# io_b.net
KiCad netlist of a schematic drawn in Altium Designer
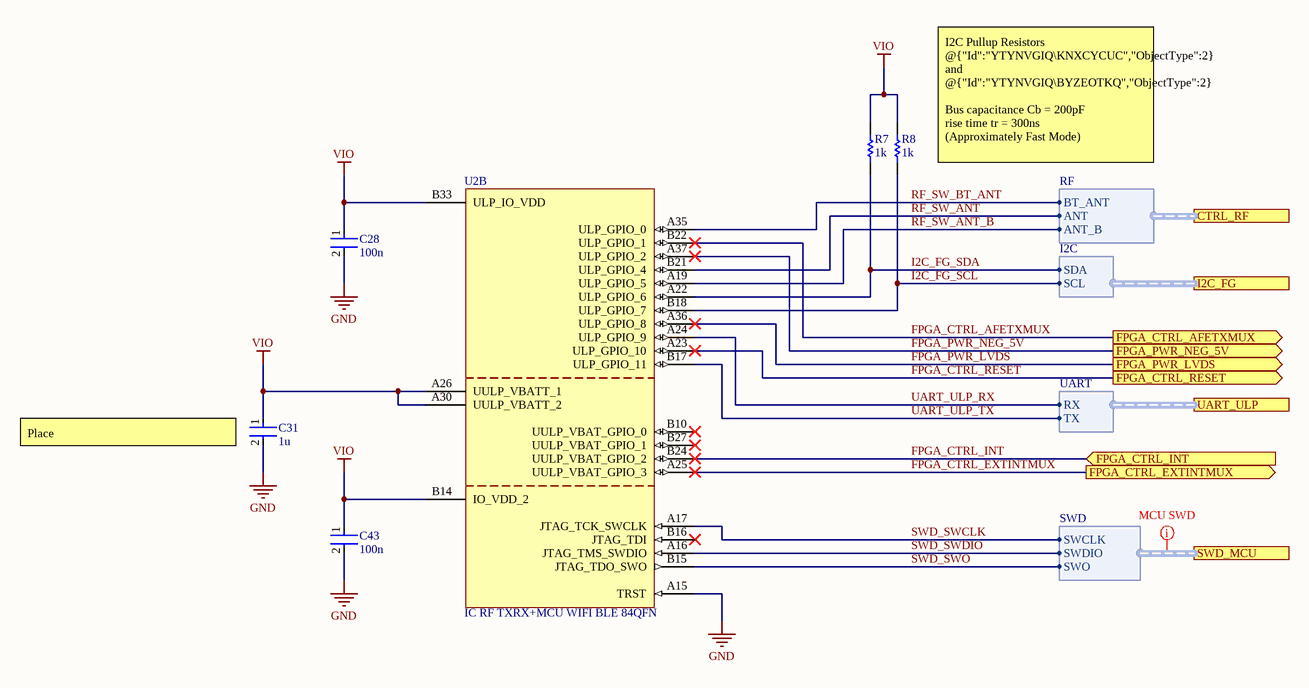
[diagram p0: io_b.SchDoc]

(export (version "E")
  (design (tool "Eeschema 10.0.6"))
  (components
    (comp (ref "C28")
      (value "100n")
      (footprint "FP-GRT155-0_05-MFG")
      (description "Multi-Layer Ceramic Capacitor 100nF 50V X7R ±10% 0402 Paper T/R")
      (libsource (lib "Altium Content Vault") (part "02cd4be3c70576c341d710602a673aa"))
    )
    (comp (ref "C31")
      (value "1u")
      (footprint "FP-GRM155-0_05-MFG")
      (description "Chip Multilayer Ceramic Capacitors for General Purpose, 0402, 1.0uF, X6S, 22%, 10%, 16V")
      (fields (field (name "TOLERANCE") "10%"))
      (libsource (lib "Altium Content Vault") (part "02cd4be3c70576c341d710602a673aa"))
    )
    (comp (ref "C43")
      (value "100n")
      (footprint "FP-GRT155-0_05-MFG")
      (description "Multi-Layer Ceramic Capacitor 100nF 50V X7R ±10% 0402 Paper T/R")
      (libsource (lib "Altium Content Vault") (part "02cd4be3c70576c341d710602a673aa"))
    )
    (comp (ref "R7")
      (value "1k")
      (footprint "RESC1005X40X25LL05T10")
      (fields (field (name "MANUFACTURER") "Yageo") (field (name "PART NUMBER") "RC0402FR-131KL"))
      (libsource (lib "Altium Content Vault") (part "RES"))
    )
    (comp (ref "R8")
      (value "1k")
      (footprint "RESC1005X40X25LL05T10")
      (fields (field (name "MANUFACTURER") "Yageo") (field (name "PART NUMBER") "RC0402FR-131KL"))
      (libsource (lib "Altium Content Vault") (part "RES"))
    )
    (comp (ref "U2")
      (value "IC RF TXRX+MCU WIFI BLE 84QFN")
      (footprint "SIWG917M110LGTBA")
      (libsource (lib "SiWG917") (part "SIWG917"))
    )
  )
  (nets
    (net (code "5") (name "/FPGA_CTRL_AFETXMUX") (class "Default")
      (node (ref "U2") (pin "B22") (pinfunction "ULP_GPIO_1_B22") (pintype "bidirectional+no_connect"))
    )
    (net (code "6") (name "/FPGA_CTRL_EXTINTMUX") (class "Default")
      (node (ref "U2") (pin "A25") (pinfunction "UULP_VBAT_GPIO_3_A25") (pintype "bidirectional+no_connect"))
    )
    (net (code "7") (name "/FPGA_CTRL_INT") (class "Default")
      (node (ref "U2") (pin "B24") (pinfunction "UULP_VBAT_GPIO_2_B24") (pintype "bidirectional+no_connect"))
    )
    (net (code "8") (name "/FPGA_CTRL_RESET") (class "Default")
      (node (ref "U2") (pin "A23") (pinfunction "ULP_GPIO_10_A23") (pintype "bidirectional+no_connect"))
    )
    (net (code "9") (name "/FPGA_PWR_LVDS") (class "Default")
      (node (ref "U2") (pin "A36") (pinfunction "ULP_GPIO_8_A36") (pintype "bidirectional+no_connect"))
    )
    (net (code "10") (name "/FPGA_PWR_NEG_5V") (class "Default")
      (node (ref "U2") (pin "A37") (pinfunction "ULP_GPIO_2_A37") (pintype "bidirectional+no_connect"))
    )
    (net (code "11") (name "/I2C_FG_SCL") (class "Default")
      (node (ref "R8") (pin "1") (pinfunction "1_1") (pintype "passive"))
      (node (ref "U2") (pin "B18") (pinfunction "ULP_GPIO_7_B18") (pintype "bidirectional"))
    )
    (net (code "12") (name "/I2C_FG_SDA") (class "Default")
      (node (ref "R7") (pin "1") (pinfunction "1_1") (pintype "passive"))
      (node (ref "U2") (pin "A22") (pinfunction "ULP_GPIO_6_A22") (pintype "bidirectional"))
    )
    (net (code "13") (name "/RF_SW_ANT") (class "Default")
      (node (ref "U2") (pin "B21") (pinfunction "ULP_GPIO_4_B21") (pintype "bidirectional"))
    )
    (net (code "14") (name "/RF_SW_ANT_B") (class "Default")
      (node (ref "U2") (pin "A19") (pinfunction "ULP_GPIO_5_A19") (pintype "bidirectional"))
    )
    (net (code "15") (name "/RF_SW_BT_ANT") (class "Default")
      (node (ref "U2") (pin "A35") (pinfunction "ULP_GPIO_0_A35") (pintype "bidirectional"))
    )
    (net (code "16") (name "/SWD_SWCLK") (class "Default")
      (node (ref "U2") (pin "A17") (pinfunction "JTAG_TCK_SWCLK_A17") (pintype "input"))
    )
    (net (code "17") (name "/SWD_SWDIO") (class "Default")
      (node (ref "U2") (pin "A16") (pinfunction "JTAG_TMS_SWDIO_A16") (pintype "input"))
    )
    (net (code "18") (name "/SWD_SWO") (class "Default")
      (node (ref "U2") (pin "B15") (pinfunction "JTAG_TDO_SWO_B15") (pintype "output"))
    )
    (net (code "19") (name "/UART_ULP_RX") (class "Default")
      (node (ref "U2") (pin "A24") (pinfunction "ULP_GPIO_9_A24") (pintype "bidirectional"))
    )
    (net (code "20") (name "/UART_ULP_TX") (class "Default")
      (node (ref "U2") (pin "B17") (pinfunction "ULP_GPIO_11_B17") (pintype "bidirectional"))
    )
    (net (code "25") (name "GND") (class "Default")
      (node (ref "C28") (pin "2") (pinfunction "2_2") (pintype "passive"))
      (node (ref "C31") (pin "2") (pinfunction "2_2") (pintype "passive"))
      (node (ref "C43") (pin "2") (pinfunction "2_2") (pintype "passive"))
      (node (ref "U2") (pin "A15") (pinfunction "TRST_A15") (pintype "input"))
    )
    (net (code "26") (name "VIO") (class "Default")
      (node (ref "C28") (pin "1") (pinfunction "1_1") (pintype "passive"))
      (node (ref "C31") (pin "1") (pinfunction "1_1") (pintype "passive"))
      (node (ref "C43") (pin "1") (pinfunction "1_1") (pintype "passive"))
      (node (ref "R7") (pin "2") (pinfunction "2_2") (pintype "passive"))
      (node (ref "R8") (pin "2") (pinfunction "2_2") (pintype "passive"))
      (node (ref "U2") (pin "A26") (pinfunction "UULP_VBATT_1_A26") (pintype "power_in"))
      (node (ref "U2") (pin "A30") (pinfunction "UULP_VBATT_2_A30") (pintype "power_in"))
      (node (ref "U2") (pin "B14") (pinfunction "IO_VDD_2_B14") (pintype "power_in"))
      (node (ref "U2") (pin "B33") (pinfunction "ULP_IO_VDD_B33") (pintype "power_in"))
    )
    (net (code "27") (name "unconnected-(U2B-JTAG_TDI-PadB16)") (class "Default")
      (node (ref "U2") (pin "B16") (pinfunction "JTAG_TDI_B16") (pintype "input+no_connect"))
    )
    (net (code "28") (name "unconnected-(U2B-UULP_VBAT_GPIO_0-PadB10)") (class "Default")
      (node (ref "U2") (pin "B10") (pinfunction "UULP_VBAT_GPIO_0_B10") (pintype "bidirectional+no_connect"))
    )
    (net (code "29") (name "unconnected-(U2B-UULP_VBAT_GPIO_1-PadB27)") (class "Default")
      (node (ref "U2") (pin "B27") (pinfunction "UULP_VBAT_GPIO_1_B27") (pintype "bidirectional+no_connect"))
    )
  )
)
